# midi-footcontroller.net
KiCad netlist of a schematic drawn in EAGLE
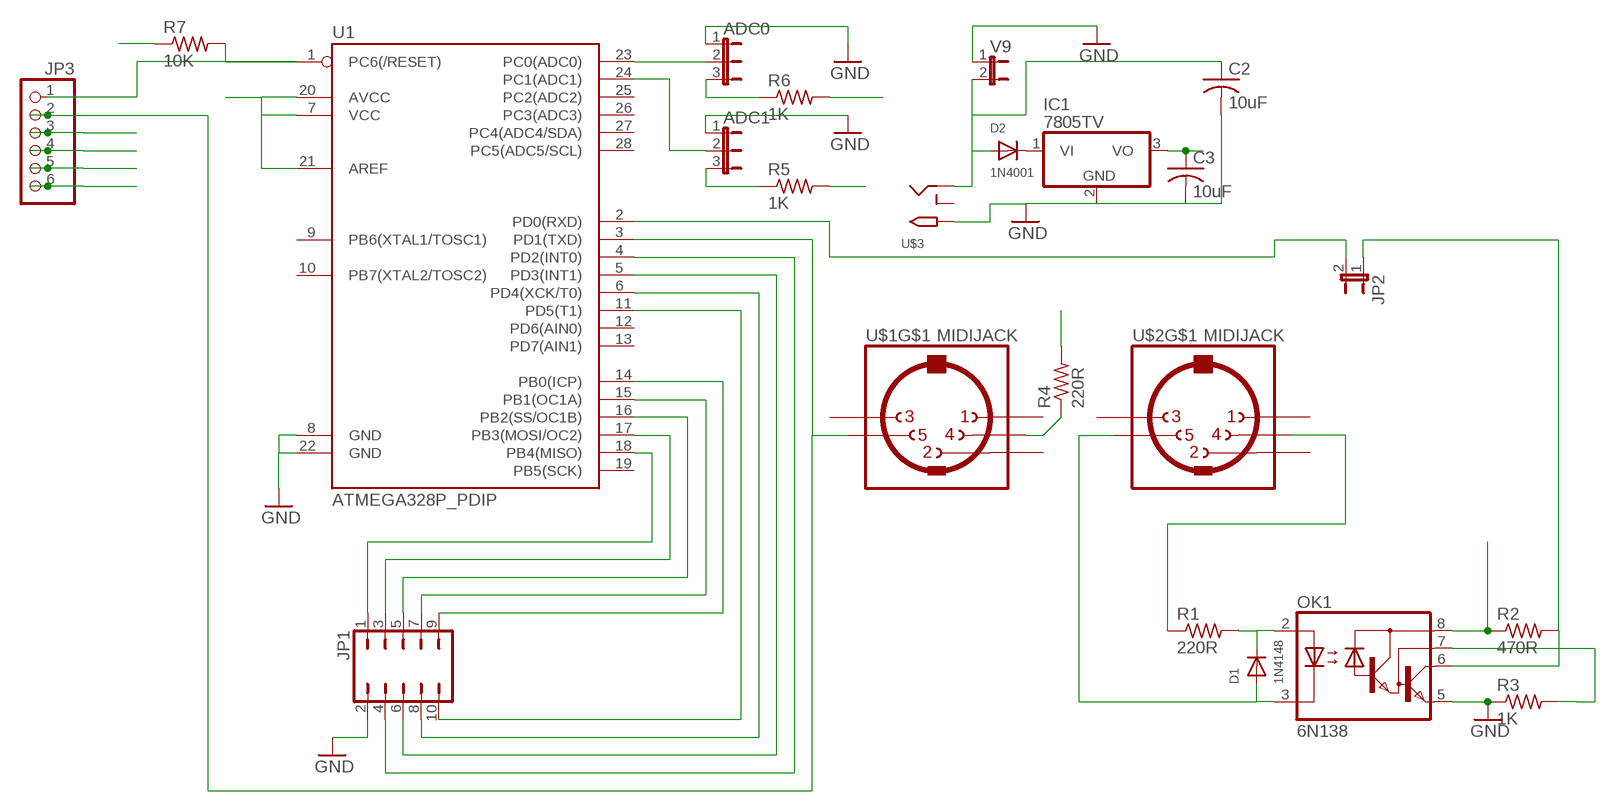
[diagram p0: schematic, sheet 1]

(export (version "E")
  (design (tool "Eeschema 10.0.6"))
  (components
    (comp (ref "ADC0")
      (value "JP2E")
      (footprint "eagle-import:JP2")
      (libsource (lib "eagle-import") (part "JP2E"))
    )
    (comp (ref "ADC1")
      (value "JP2E")
      (footprint "eagle-import:JP2")
      (libsource (lib "eagle-import") (part "JP2E"))
    )
    (comp (ref "C2")
      (value "10uF")
      (footprint "eagle-import:C025-025X050")
      (libsource (lib "eagle-import") (part "C-US025-025X050"))
    )
    (comp (ref "C3")
      (value "10uF")
      (footprint "eagle-import:C025-025X050")
      (libsource (lib "eagle-import") (part "C-US025-025X050"))
    )
    (comp (ref "D1")
      (value "1N4148")
      (footprint "eagle-import:DO-1N4148")
      (libsource (lib "eagle-import") (part "DIODEDO-1N4148"))
    )
    (comp (ref "D2")
      (value "1N4001")
      (footprint "eagle-import:DO-1N4148")
      (libsource (lib "eagle-import") (part "DIODEDO-1N4148"))
    )
    (comp (ref "IC1")
      (value "7805TV")
      (footprint "eagle-import:TO220V")
      (libsource (lib "eagle-import") (part "78TV05"))
    )
    (comp (ref "JP1")
      (value "JP5Q")
      (footprint "eagle-import:JP5Q")
      (libsource (lib "eagle-import") (part "JP5Q"))
    )
    (comp (ref "JP2")
      (value "JP1E")
      (footprint "eagle-import:JP1")
      (libsource (lib "eagle-import") (part "JP1E"))
    )
    (comp (ref "JP3")
      (value "PINHD-1X6LOCK")
      (footprint "eagle-import:1X06-BIGLOCK")
      (libsource (lib "eagle-import") (part "PINHD-1X6LOCK"))
    )
    (comp (ref "OK1")
      (value "6N138")
      (footprint "eagle-import:DIL08")
      (fields (field (name "MF") "VISHAY/TELEFUNKEN"))
      (libsource (lib "eagle-import") (part "6N138"))
    )
    (comp (ref "R1")
      (value "220R")
      (footprint "eagle-import:0207_9")
      (libsource (lib "eagle-import") (part "R-US_0207/9"))
    )
    (comp (ref "R2")
      (value "470R")
      (footprint "eagle-import:0207_9")
      (libsource (lib "eagle-import") (part "R-US_0207/9"))
    )
    (comp (ref "R3")
      (value "1K")
      (footprint "eagle-import:0207_9")
      (libsource (lib "eagle-import") (part "R-US_0207/9"))
    )
    (comp (ref "R4")
      (value "220R")
      (footprint "eagle-import:0207_9")
      (libsource (lib "eagle-import") (part "R-US_0207/9"))
    )
    (comp (ref "R5")
      (value "1K")
      (footprint "eagle-import:0207_9")
      (libsource (lib "eagle-import") (part "R-US_0207/9"))
    )
    (comp (ref "R6")
      (value "1K")
      (footprint "eagle-import:0207_9")
      (libsource (lib "eagle-import") (part "R-US_0207/9"))
    )
    (comp (ref "R7")
      (value "10K")
      (footprint "eagle-import:0207_9")
      (libsource (lib "eagle-import") (part "R-US_0207/9"))
    )
    (comp (ref "U$1")
      (value "MIDIJACK")
      (footprint "eagle-import:CP-2350")
      (libsource (lib "eagle-import") (part "MIDIJACK"))
    )
    (comp (ref "U$2")
      (value "MIDIJACK")
      (footprint "eagle-import:CP-2350")
      (libsource (lib "eagle-import") (part "MIDIJACK"))
    )
    (comp (ref "U$3")
      (value "2.1MMJACKTHM")
      (footprint "eagle-import:PJ-102A")
      (libsource (lib "eagle-import") (part "2.1MMJACKTHM"))
    )
    (comp (ref "U1")
      (value "ATMEGA328P_PDIP")
      (footprint "eagle-import:DIL28-3")
      (libsource (lib "eagle-import") (part "ATMEGA328P_PDIP"))
    )
    (comp (ref "V9")
      (value "JP1E")
      (footprint "eagle-import:JP1")
      (libsource (lib "eagle-import") (part "JP1E"))
    )
  )
  (nets
    (net (code "1") (name "/RXD") (class "Default")
      (node (ref "JP2") (pin "2") (pinfunction "2_2") (pintype "passive"))
      (node (ref "JP3") (pin "3") (pinfunction "3_3") (pintype "passive"))
      (node (ref "U1") (pin "2") (pinfunction "PD0(RXD)_2") (pintype "bidirectional"))
    )
    (net (code "2") (name "/V5") (class "Default")
      (node (ref "C3") (pin "1") (pinfunction "1_1") (pintype "passive"))
      (node (ref "IC1") (pin "3") (pinfunction "VO_3") (pintype "passive"))
      (node (ref "JP3") (pin "4") (pinfunction "4_4") (pintype "passive"))
      (node (ref "OK1") (pin "8") (pinfunction "VCC_8") (pintype "passive"))
      (node (ref "R2") (pin "1") (pinfunction "1_1") (pintype "passive"))
      (node (ref "R4") (pin "2") (pinfunction "2_2") (pintype "passive"))
      (node (ref "R5") (pin "2") (pinfunction "2_2") (pintype "passive"))
      (node (ref "R6") (pin "2") (pinfunction "2_2") (pintype "passive"))
      (node (ref "R7") (pin "1") (pinfunction "1_1") (pintype "passive"))
      (node (ref "U1") (pin "20") (pinfunction "AVCC_20") (pintype "bidirectional"))
      (node (ref "U1") (pin "21") (pinfunction "AREF_21") (pintype "bidirectional"))
      (node (ref "U1") (pin "7") (pinfunction "VCC_7") (pintype "bidirectional"))
    )
    (net (code "3") (name "GND") (class "Default")
      (node (ref "ADC0") (pin "1") (pinfunction "1_1") (pintype "passive"))
      (node (ref "ADC1") (pin "1") (pinfunction "1_1") (pintype "passive"))
      (node (ref "C2") (pin "2") (pinfunction "2_2") (pintype "passive"))
      (node (ref "C3") (pin "2") (pinfunction "2_2") (pintype "passive"))
      (node (ref "IC1") (pin "2") (pinfunction "GND_2") (pintype "passive"))
      (node (ref "JP1") (pin "2") (pinfunction "2_2") (pintype "passive"))
      (node (ref "JP3") (pin "5") (pinfunction "5_5") (pintype "passive"))
      (node (ref "OK1") (pin "5") (pinfunction "GND_5") (pintype "passive"))
      (node (ref "R3") (pin "1") (pinfunction "1_1") (pintype "passive"))
      (node (ref "U$3") (pin "TIP") (pinfunction "TIP_TIP") (pintype "bidirectional"))
      (node (ref "U1") (pin "22") (pinfunction "GND_22") (pintype "bidirectional"))
      (node (ref "U1") (pin "8") (pinfunction "GND_8") (pintype "bidirectional"))
      (node (ref "V9") (pin "1") (pinfunction "1_1") (pintype "passive"))
    )
    (net (code "4") (name "Net-(ADC0-Pad3)") (class "Default")
      (node (ref "ADC0") (pin "3") (pinfunction "3_3") (pintype "passive"))
      (node (ref "R6") (pin "1") (pinfunction "1_1") (pintype "passive"))
    )
    (net (code "5") (name "Net-(ADC1-Pad3)") (class "Default")
      (node (ref "ADC1") (pin "3") (pinfunction "3_3") (pintype "passive"))
      (node (ref "R5") (pin "1") (pinfunction "1_1") (pintype "passive"))
    )
    (net (code "6") (name "Net-(C2-Pad1)") (class "Default")
      (node (ref "C2") (pin "1") (pinfunction "1_1") (pintype "passive"))
      (node (ref "D2") (pin "A") (pinfunction "A_A") (pintype "passive"))
      (node (ref "U$3") (pin "RING") (pinfunction "RING_RING") (pintype "bidirectional"))
      (node (ref "V9") (pin "2") (pinfunction "2_2") (pintype "passive"))
    )
    (net (code "7") (name "Net-(IC1-VI)") (class "Default")
      (node (ref "D2") (pin "C") (pinfunction "C_C") (pintype "passive"))
      (node (ref "IC1") (pin "1") (pinfunction "VI_1") (pintype "input"))
    )
    (net (code "8") (name "Net-(OK1-A)") (class "Default")
      (node (ref "D1") (pin "C") (pinfunction "C_C") (pintype "passive"))
      (node (ref "OK1") (pin "2") (pinfunction "A_2") (pintype "passive"))
      (node (ref "R1") (pin "2") (pinfunction "2_2") (pintype "passive"))
    )
    (net (code "9") (name "Net-(OK1-C)") (class "Default")
      (node (ref "D1") (pin "A") (pinfunction "A_A") (pintype "passive"))
      (node (ref "OK1") (pin "3") (pinfunction "C_3") (pintype "passive"))
      (node (ref "U$2") (pin "5") (pinfunction "5_5") (pintype "passive"))
    )
    (net (code "10") (name "Net-(OK1-VB)") (class "Default")
      (node (ref "OK1") (pin "7") (pinfunction "VB_7") (pintype "passive"))
      (node (ref "R3") (pin "2") (pinfunction "2_2") (pintype "passive"))
    )
    (net (code "11") (name "Net-(OK1-VO)") (class "Default")
      (node (ref "JP2") (pin "1") (pinfunction "1_1") (pintype "passive"))
      (node (ref "OK1") (pin "6") (pinfunction "VO_6") (pintype "passive"))
      (node (ref "R2") (pin "2") (pinfunction "2_2") (pintype "passive"))
    )
    (net (code "12") (name "Net-(R1-Pad1)") (class "Default")
      (node (ref "R1") (pin "1") (pinfunction "1_1") (pintype "passive"))
      (node (ref "U$2") (pin "4") (pinfunction "4_4") (pintype "passive"))
    )
    (net (code "13") (name "Net-(R4-Pad1)") (class "Default")
      (node (ref "R4") (pin "1") (pinfunction "1_1") (pintype "passive"))
      (node (ref "U$1") (pin "4") (pinfunction "4_4") (pintype "passive"))
    )
    (net (code "14") (name "Net-(U1-PB0(ICP))") (class "Default")
      (node (ref "JP1") (pin "9") (pinfunction "9_9") (pintype "passive"))
      (node (ref "U1") (pin "14") (pinfunction "PB0(ICP)_14") (pintype "bidirectional"))
    )
    (net (code "15") (name "Net-(U1-PB1(OC1A))") (class "Default")
      (node (ref "JP1") (pin "7") (pinfunction "7_7") (pintype "passive"))
      (node (ref "U1") (pin "15") (pinfunction "PB1(OC1A)_15") (pintype "bidirectional"))
    )
    (net (code "16") (name "Net-(U1-PB2(SS{slash}OC1B))") (class "Default")
      (node (ref "JP1") (pin "5") (pinfunction "5_5") (pintype "passive"))
      (node (ref "U1") (pin "16") (pinfunction "PB2(SS/OC1B)_16") (pintype "bidirectional"))
    )
    (net (code "17") (name "Net-(U1-PB3(MOSI{slash}OC2))") (class "Default")
      (node (ref "JP1") (pin "3") (pinfunction "3_3") (pintype "passive"))
      (node (ref "U1") (pin "17") (pinfunction "PB3(MOSI/OC2)_17") (pintype "bidirectional"))
    )
    (net (code "18") (name "Net-(U1-PB4(MISO))") (class "Default")
      (node (ref "JP1") (pin "1") (pinfunction "1_1") (pintype "passive"))
      (node (ref "U1") (pin "18") (pinfunction "PB4(MISO)_18") (pintype "bidirectional"))
    )
    (net (code "19") (name "Net-(U1-PC0(ADC0))") (class "Default")
      (node (ref "ADC0") (pin "2") (pinfunction "2_2") (pintype "passive"))
      (node (ref "U1") (pin "23") (pinfunction "PC0(ADC0)_23") (pintype "bidirectional"))
    )
    (net (code "20") (name "Net-(U1-PC1(ADC1))") (class "Default")
      (node (ref "ADC1") (pin "2") (pinfunction "2_2") (pintype "passive"))
      (node (ref "U1") (pin "24") (pinfunction "PC1(ADC1)_24") (pintype "bidirectional"))
    )
    (net (code "21") (name "Net-(U1-PC6({slash}RESET))") (class "Default")
      (node (ref "JP3") (pin "1") (pinfunction "1_1") (pintype "passive"))
      (node (ref "R7") (pin "2") (pinfunction "2_2") (pintype "passive"))
      (node (ref "U1") (pin "1") (pinfunction "PC6(/RESET)_1") (pintype "bidirectional"))
    )
    (net (code "22") (name "Net-(U1-PD1(TXD))") (class "Default")
      (node (ref "JP3") (pin "2") (pinfunction "2_2") (pintype "passive"))
      (node (ref "U$1") (pin "5") (pinfunction "5_5") (pintype "passive"))
      (node (ref "U1") (pin "3") (pinfunction "PD1(TXD)_3") (pintype "bidirectional"))
    )
    (net (code "23") (name "Net-(U1-PD2(INT0))") (class "Default")
      (node (ref "JP1") (pin "4") (pinfunction "4_4") (pintype "passive"))
      (node (ref "U1") (pin "4") (pinfunction "PD2(INT0)_4") (pintype "bidirectional"))
    )
    (net (code "24") (name "Net-(U1-PD3(INT1))") (class "Default")
      (node (ref "JP1") (pin "6") (pinfunction "6_6") (pintype "passive"))
      (node (ref "U1") (pin "5") (pinfunction "PD3(INT1)_5") (pintype "bidirectional"))
    )
    (net (code "25") (name "Net-(U1-PD4(XCK{slash}T0))") (class "Default")
      (node (ref "JP1") (pin "8") (pinfunction "8_8") (pintype "passive"))
      (node (ref "U1") (pin "6") (pinfunction "PD4(XCK/T0)_6") (pintype "bidirectional"))
    )
    (net (code "26") (name "Net-(U1-PD5(T1))") (class "Default")
      (node (ref "JP1") (pin "10") (pinfunction "10_10") (pintype "passive"))
      (node (ref "U1") (pin "11") (pinfunction "PD5(T1)_11") (pintype "bidirectional"))
    )
    (net (code "27") (name "unconnected-(JP3-Pad6)") (class "Default")
      (node (ref "JP3") (pin "6") (pinfunction "6_6") (pintype "passive"))
    )
    (net (code "28") (name "unconnected-(U$1-Pad1)") (class "Default")
      (node (ref "U$1") (pin "1") (pinfunction "1_1") (pintype "passive"))
    )
    (net (code "29") (name "unconnected-(U$1-Pad2)") (class "Default")
      (node (ref "U$1") (pin "2") (pinfunction "2_2") (pintype "passive"))
    )
    (net (code "30") (name "unconnected-(U$1-Pad3)") (class "Default")
      (node (ref "U$1") (pin "3") (pinfunction "3_3") (pintype "passive"))
    )
    (net (code "31") (name "unconnected-(U$2-Pad1)") (class "Default")
      (node (ref "U$2") (pin "1") (pinfunction "1_1") (pintype "passive"))
    )
    (net (code "32") (name "unconnected-(U$2-Pad2)") (class "Default")
      (node (ref "U$2") (pin "2") (pinfunction "2_2") (pintype "passive"))
    )
    (net (code "33") (name "unconnected-(U$2-Pad3)") (class "Default")
      (node (ref "U$2") (pin "3") (pinfunction "3_3") (pintype "passive"))
    )
    (net (code "34") (name "unconnected-(U$3-PadRING_SW)") (class "Default")
      (node (ref "U$3") (pin "RING_SW") (pinfunction "RING_SW_RING_SW") (pintype "bidirectional"))
    )
    (net (code "35") (name "unconnected-(U1-PB5(SCK)-Pad19)") (class "Default")
      (node (ref "U1") (pin "19") (pinfunction "PB5(SCK)_19") (pintype "bidirectional"))
    )
    (net (code "36") (name "unconnected-(U1-PB6(XTAL1{slash}TOSC1)-Pad9)") (class "Default")
      (node (ref "U1") (pin "9") (pinfunction "PB6(XTAL1/TOSC1)_9") (pintype "bidirectional"))
    )
    (net (code "37") (name "unconnected-(U1-PB7(XTAL2{slash}TOSC2)-Pad10)") (class "Default")
      (node (ref "U1") (pin "10") (pinfunction "PB7(XTAL2/TOSC2)_10") (pintype "bidirectional"))
    )
    (net (code "38") (name "unconnected-(U1-PC2(ADC2)-Pad25)") (class "Default")
      (node (ref "U1") (pin "25") (pinfunction "PC2(ADC2)_25") (pintype "bidirectional"))
    )
    (net (code "39") (name "unconnected-(U1-PC3(ADC3)-Pad26)") (class "Default")
      (node (ref "U1") (pin "26") (pinfunction "PC3(ADC3)_26") (pintype "bidirectional"))
    )
    (net (code "40") (name "unconnected-(U1-PC4(ADC4{slash}SDA)-Pad27)") (class "Default")
      (node (ref "U1") (pin "27") (pinfunction "PC4(ADC4/SDA)_27") (pintype "bidirectional"))
    )
    (net (code "41") (name "unconnected-(U1-PC5(ADC5{slash}SCL)-Pad28)") (class "Default")
      (node (ref "U1") (pin "28") (pinfunction "PC5(ADC5/SCL)_28") (pintype "bidirectional"))
    )
    (net (code "42") (name "unconnected-(U1-PD6(AIN0)-Pad12)") (class "Default")
      (node (ref "U1") (pin "12") (pinfunction "PD6(AIN0)_12") (pintype "bidirectional"))
    )
    (net (code "43") (name "unconnected-(U1-PD7(AIN1)-Pad13)") (class "Default")
      (node (ref "U1") (pin "13") (pinfunction "PD7(AIN1)_13") (pintype "bidirectional"))
    )
  )
)
